# RPiHat.net
KiCad netlist of a schematic drawn in EasyEDA
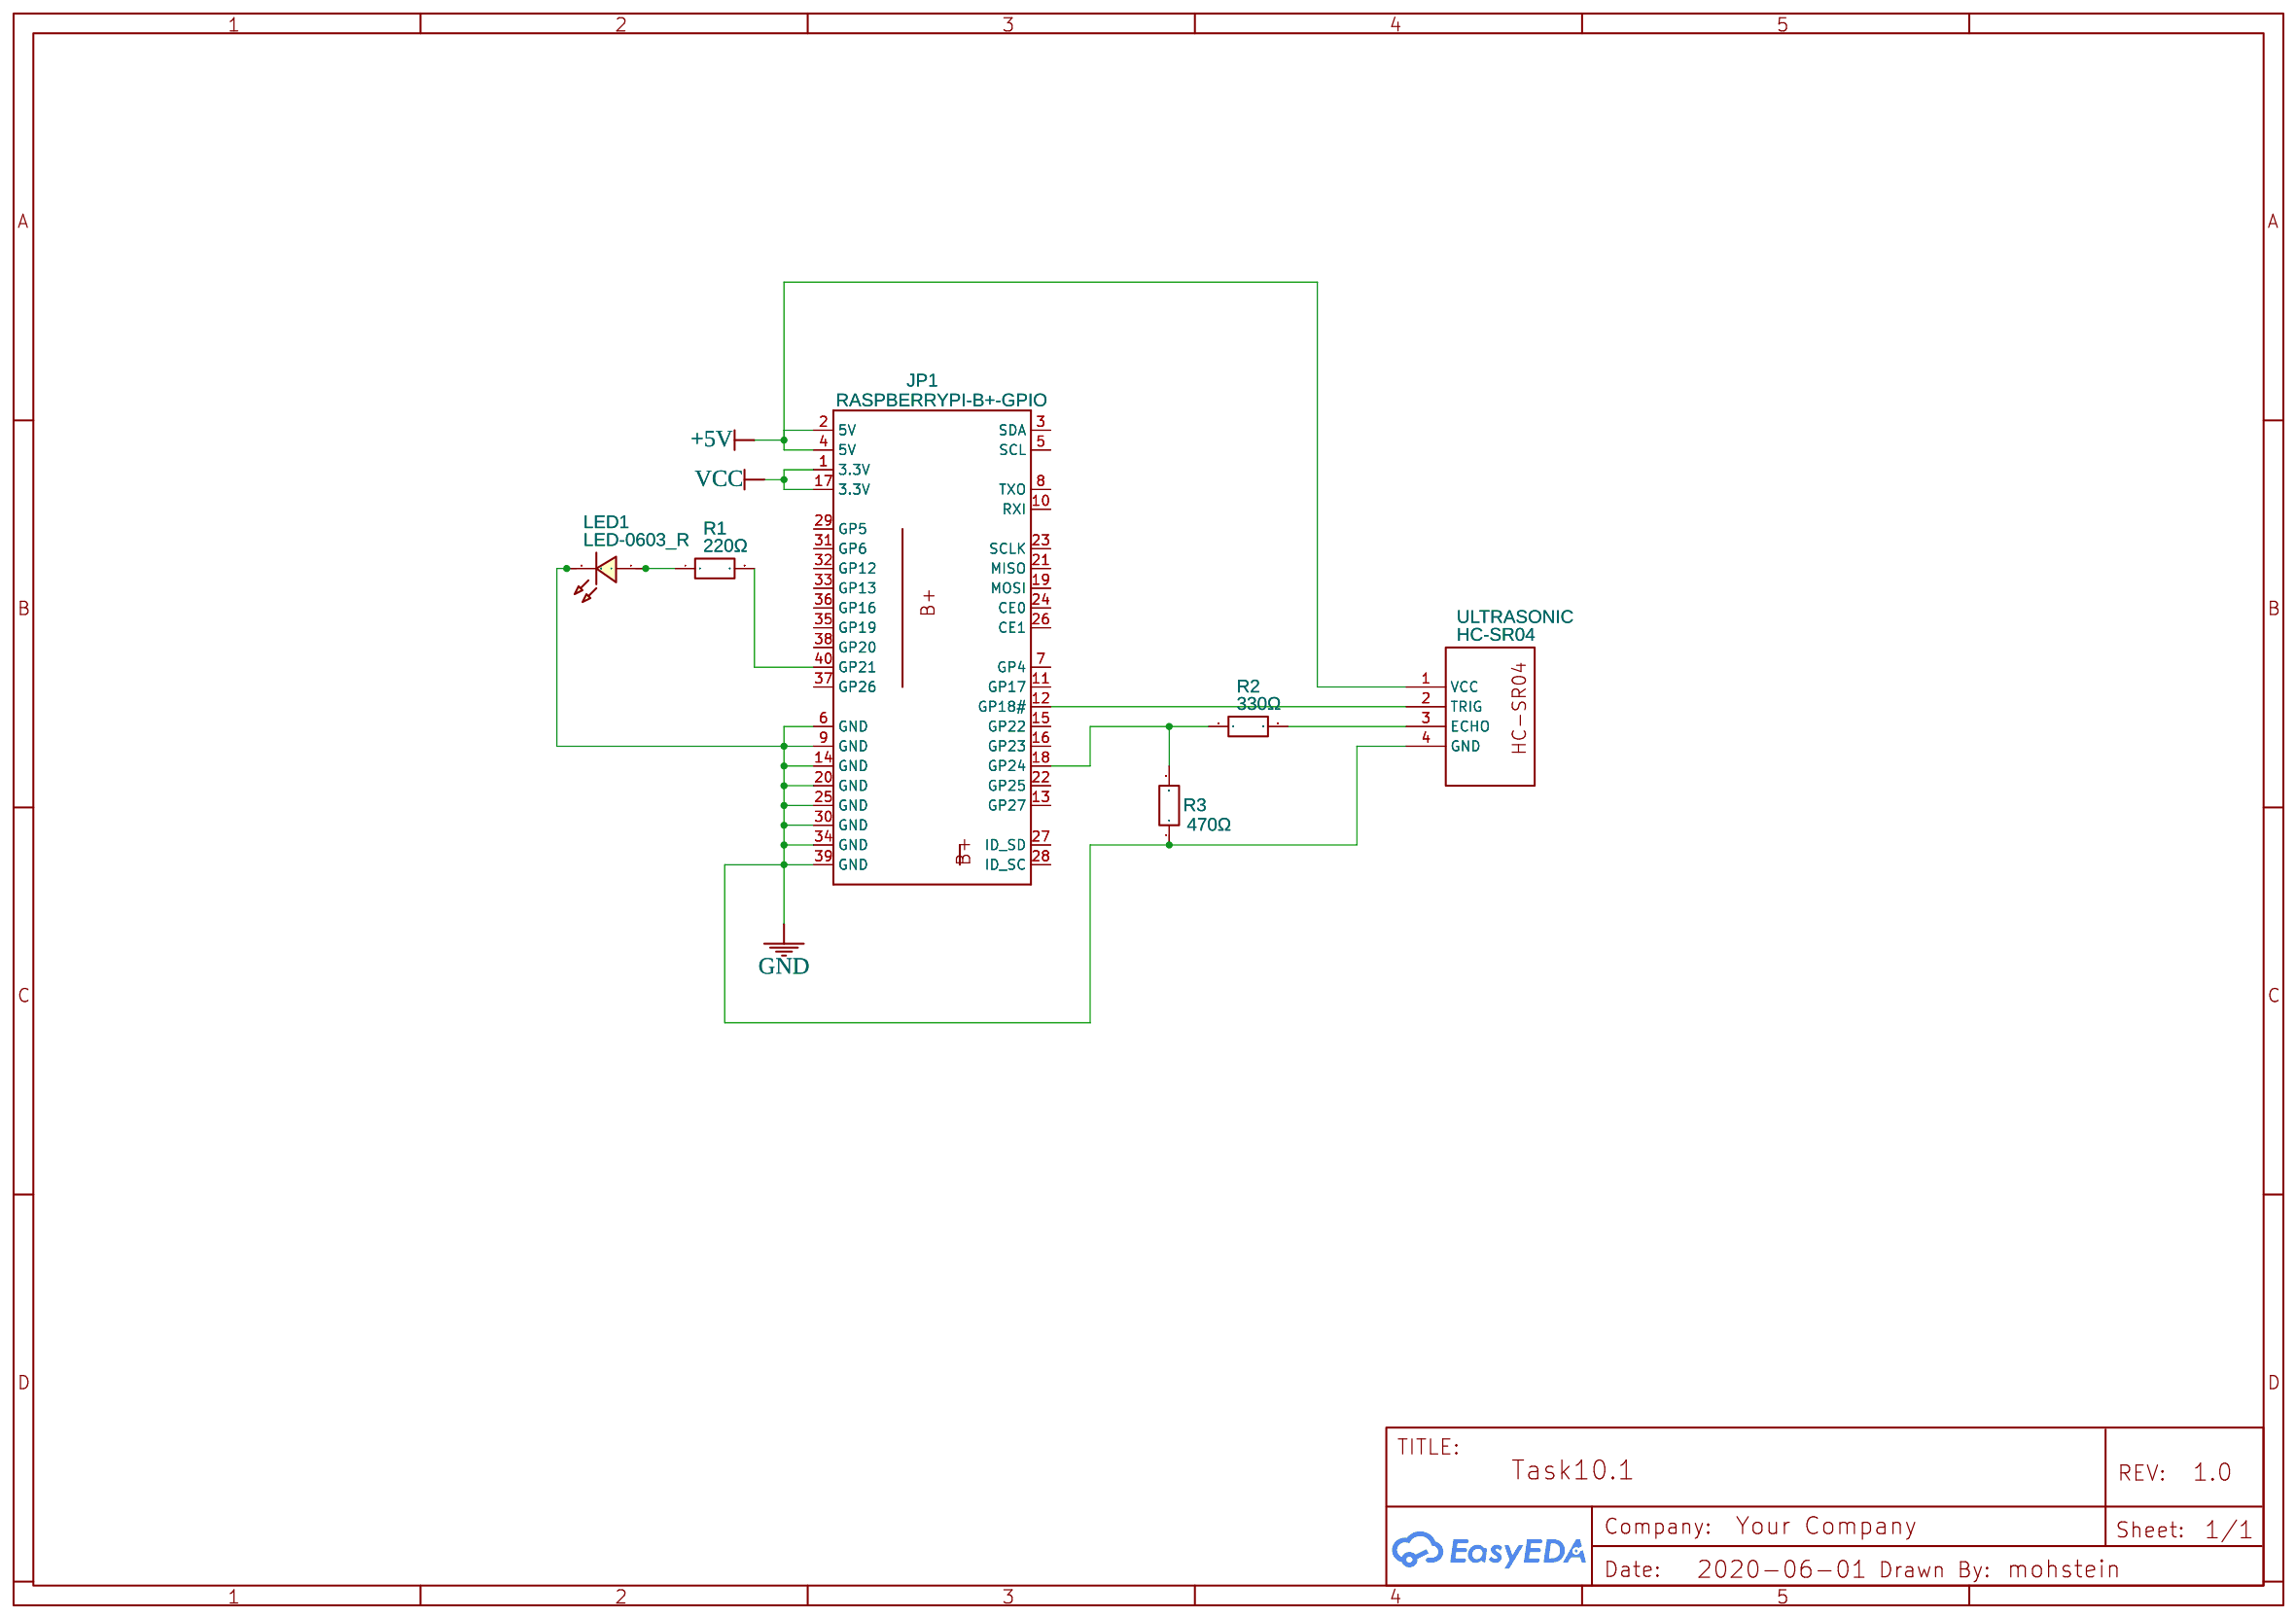
[diagram p0: schematic sheet]

(export (version "E")
  (design (tool "Eeschema 10.0.6"))
  (components
    (comp (ref "JP1") (value "RASPBERRYPI-B+-GPIO") (libsource (lib "") (part "RASPBERRYPI-B+-GPIO")))
    (comp (ref "LED1")
      (value "LED-0603_R")
      (fields
        (field (name "BOM_Manufacturer Part") "19-217/R6C-AL1M2VY/3T")
        (field (name "BOM_Supplier Part") "C72044")
      )
      (libsource (lib "") (part "LED-0603_R"))
    )
    (comp (ref "R1") (value "220Ω") (libsource (lib "") (part "R_0402_EU")))
    (comp (ref "R2") (value "330Ω") (libsource (lib "") (part "R_0402_EU")))
    (comp (ref "R3") (value "470Ω") (libsource (lib "") (part "R_0402_EU_1")))
    (comp (ref "ULTRASONIC") (value "HC-SR04") (libsource (lib "") (part "HC-SR04")))
  )
  (nets
    (net (code "1") (name "+5V") (class "Default")
      (node (ref "JP1") (pin "2") (pinfunction "5V_2") (pintype "passive"))
      (node (ref "JP1") (pin "4") (pinfunction "5V_4") (pintype "passive"))
      (node (ref "ULTRASONIC") (pin "1") (pinfunction "VCC_1") (pintype "unspecified"))
    )
    (net (code "2") (name "GND") (class "Default")
      (node (ref "JP1") (pin "14") (pinfunction "GND_14") (pintype "passive"))
      (node (ref "JP1") (pin "20") (pinfunction "GND_20") (pintype "passive"))
      (node (ref "JP1") (pin "25") (pinfunction "GND_25") (pintype "passive"))
      (node (ref "JP1") (pin "30") (pinfunction "GND_30") (pintype "passive"))
      (node (ref "JP1") (pin "34") (pinfunction "GND_34") (pintype "passive"))
      (node (ref "JP1") (pin "39") (pinfunction "GND_39") (pintype "passive"))
      (node (ref "JP1") (pin "6") (pinfunction "GND_6") (pintype "passive"))
      (node (ref "JP1") (pin "9") (pinfunction "GND_9") (pintype "passive"))
      (node (ref "LED1") (pin "2") (pinfunction "2_2") (pintype "unspecified"))
      (node (ref "R3") (pin "1") (pinfunction "1_1") (pintype "unspecified"))
      (node (ref "ULTRASONIC") (pin "4") (pinfunction "GND_4") (pintype "unspecified"))
    )
    (net (code "3") (name "Net-(JP1-GP18#)") (class "Default")
      (node (ref "JP1") (pin "12") (pinfunction "GP18#_12") (pintype "unspecified"))
      (node (ref "ULTRASONIC") (pin "2") (pinfunction "TRIG_2") (pintype "unspecified"))
    )
    (net (code "4") (name "Net-(JP1-GP21)") (class "Default")
      (node (ref "JP1") (pin "40") (pinfunction "GP21_40") (pintype "unspecified"))
      (node (ref "R1") (pin "2") (pinfunction "2_2") (pintype "unspecified"))
    )
    (net (code "5") (name "Net-(JP1-GP24)") (class "Default")
      (node (ref "JP1") (pin "18") (pinfunction "GP24_18") (pintype "unspecified"))
      (node (ref "R2") (pin "1") (pinfunction "1_1") (pintype "unspecified"))
      (node (ref "R3") (pin "2") (pinfunction "2_2") (pintype "unspecified"))
    )
    (net (code "6") (name "Net-(LED1-Pad1)") (class "Default")
      (node (ref "LED1") (pin "1") (pinfunction "1_1") (pintype "unspecified"))
      (node (ref "R1") (pin "1") (pinfunction "1_1") (pintype "unspecified"))
    )
    (net (code "7") (name "Net-(ULTRASONIC-ECHO)") (class "Default")
      (node (ref "R2") (pin "2") (pinfunction "2_2") (pintype "unspecified"))
      (node (ref "ULTRASONIC") (pin "3") (pinfunction "ECHO_3") (pintype "unspecified"))
    )
    (net (code "8") (name "VCC") (class "Default")
      (node (ref "JP1") (pin "1") (pinfunction "3.3V_1") (pintype "passive"))
      (node (ref "JP1") (pin "17") (pinfunction "3.3V_17") (pintype "passive"))
    )
    (net (code "9") (name "unconnected-(JP1-CE0-Pad24)") (class "Default")
      (node (ref "JP1") (pin "24") (pinfunction "CE0_24") (pintype "output"))
    )
    (net (code "10") (name "unconnected-(JP1-CE1-Pad26)") (class "Default")
      (node (ref "JP1") (pin "26") (pinfunction "CE1_26") (pintype "output"))
    )
    (net (code "11") (name "unconnected-(JP1-GP4-Pad7)") (class "Default")
      (node (ref "JP1") (pin "7") (pinfunction "GP4_7") (pintype "unspecified"))
    )
    (net (code "12") (name "unconnected-(JP1-GP5-Pad29)") (class "Default")
      (node (ref "JP1") (pin "29") (pinfunction "GP5_29") (pintype "unspecified"))
    )
    (net (code "13") (name "unconnected-(JP1-GP6-Pad31)") (class "Default")
      (node (ref "JP1") (pin "31") (pinfunction "GP6_31") (pintype "unspecified"))
    )
    (net (code "14") (name "unconnected-(JP1-GP12-Pad32)") (class "Default")
      (node (ref "JP1") (pin "32") (pinfunction "GP12_32") (pintype "unspecified"))
    )
    (net (code "15") (name "unconnected-(JP1-GP13-Pad33)") (class "Default")
      (node (ref "JP1") (pin "33") (pinfunction "GP13_33") (pintype "unspecified"))
    )
    (net (code "16") (name "unconnected-(JP1-GP16-Pad36)") (class "Default")
      (node (ref "JP1") (pin "36") (pinfunction "GP16_36") (pintype "unspecified"))
    )
    (net (code "17") (name "unconnected-(JP1-GP17-Pad11)") (class "Default")
      (node (ref "JP1") (pin "11") (pinfunction "GP17_11") (pintype "unspecified"))
    )
    (net (code "18") (name "unconnected-(JP1-GP19-Pad35)") (class "Default")
      (node (ref "JP1") (pin "35") (pinfunction "GP19_35") (pintype "unspecified"))
    )
    (net (code "19") (name "unconnected-(JP1-GP20-Pad38)") (class "Default")
      (node (ref "JP1") (pin "38") (pinfunction "GP20_38") (pintype "unspecified"))
    )
    (net (code "20") (name "unconnected-(JP1-GP22-Pad15)") (class "Default")
      (node (ref "JP1") (pin "15") (pinfunction "GP22_15") (pintype "unspecified"))
    )
    (net (code "21") (name "unconnected-(JP1-GP23-Pad16)") (class "Default")
      (node (ref "JP1") (pin "16") (pinfunction "GP23_16") (pintype "unspecified"))
    )
    (net (code "22") (name "unconnected-(JP1-GP25-Pad22)") (class "Default")
      (node (ref "JP1") (pin "22") (pinfunction "GP25_22") (pintype "unspecified"))
    )
    (net (code "23") (name "unconnected-(JP1-GP26-Pad37)") (class "Default")
      (node (ref "JP1") (pin "37") (pinfunction "GP26_37") (pintype "unspecified"))
    )
    (net (code "24") (name "unconnected-(JP1-GP27-Pad13)") (class "Default")
      (node (ref "JP1") (pin "13") (pinfunction "GP27_13") (pintype "unspecified"))
    )
    (net (code "25") (name "unconnected-(JP1-ID_SC-Pad28)") (class "Default")
      (node (ref "JP1") (pin "28") (pinfunction "ID_SC_28") (pintype "unspecified"))
    )
    (net (code "26") (name "unconnected-(JP1-ID_SD-Pad27)") (class "Default")
      (node (ref "JP1") (pin "27") (pinfunction "ID_SD_27") (pintype "unspecified"))
    )
    (net (code "27") (name "unconnected-(JP1-MISO-Pad21)") (class "Default")
      (node (ref "JP1") (pin "21") (pinfunction "MISO_21") (pintype "input"))
    )
    (net (code "28") (name "unconnected-(JP1-MOSI-Pad19)") (class "Default")
      (node (ref "JP1") (pin "19") (pinfunction "MOSI_19") (pintype "output"))
    )
    (net (code "29") (name "unconnected-(JP1-RXI-Pad10)") (class "Default")
      (node (ref "JP1") (pin "10") (pinfunction "RXI_10") (pintype "input"))
    )
    (net (code "30") (name "unconnected-(JP1-SCL-Pad5)") (class "Default")
      (node (ref "JP1") (pin "5") (pinfunction "SCL_5") (pintype "unspecified"))
    )
    (net (code "31") (name "unconnected-(JP1-SCLK-Pad23)") (class "Default")
      (node (ref "JP1") (pin "23") (pinfunction "SCLK_23") (pintype "output"))
    )
    (net (code "32") (name "unconnected-(JP1-SDA-Pad3)") (class "Default")
      (node (ref "JP1") (pin "3") (pinfunction "SDA_3") (pintype "unspecified"))
    )
    (net (code "33") (name "unconnected-(JP1-TXO-Pad8)") (class "Default")
      (node (ref "JP1") (pin "8") (pinfunction "TXO_8") (pintype "output"))
    )
  )
)
